# USB-8452_flash_breakout.net
KiCad netlist of a schematic drawn in EAGLE
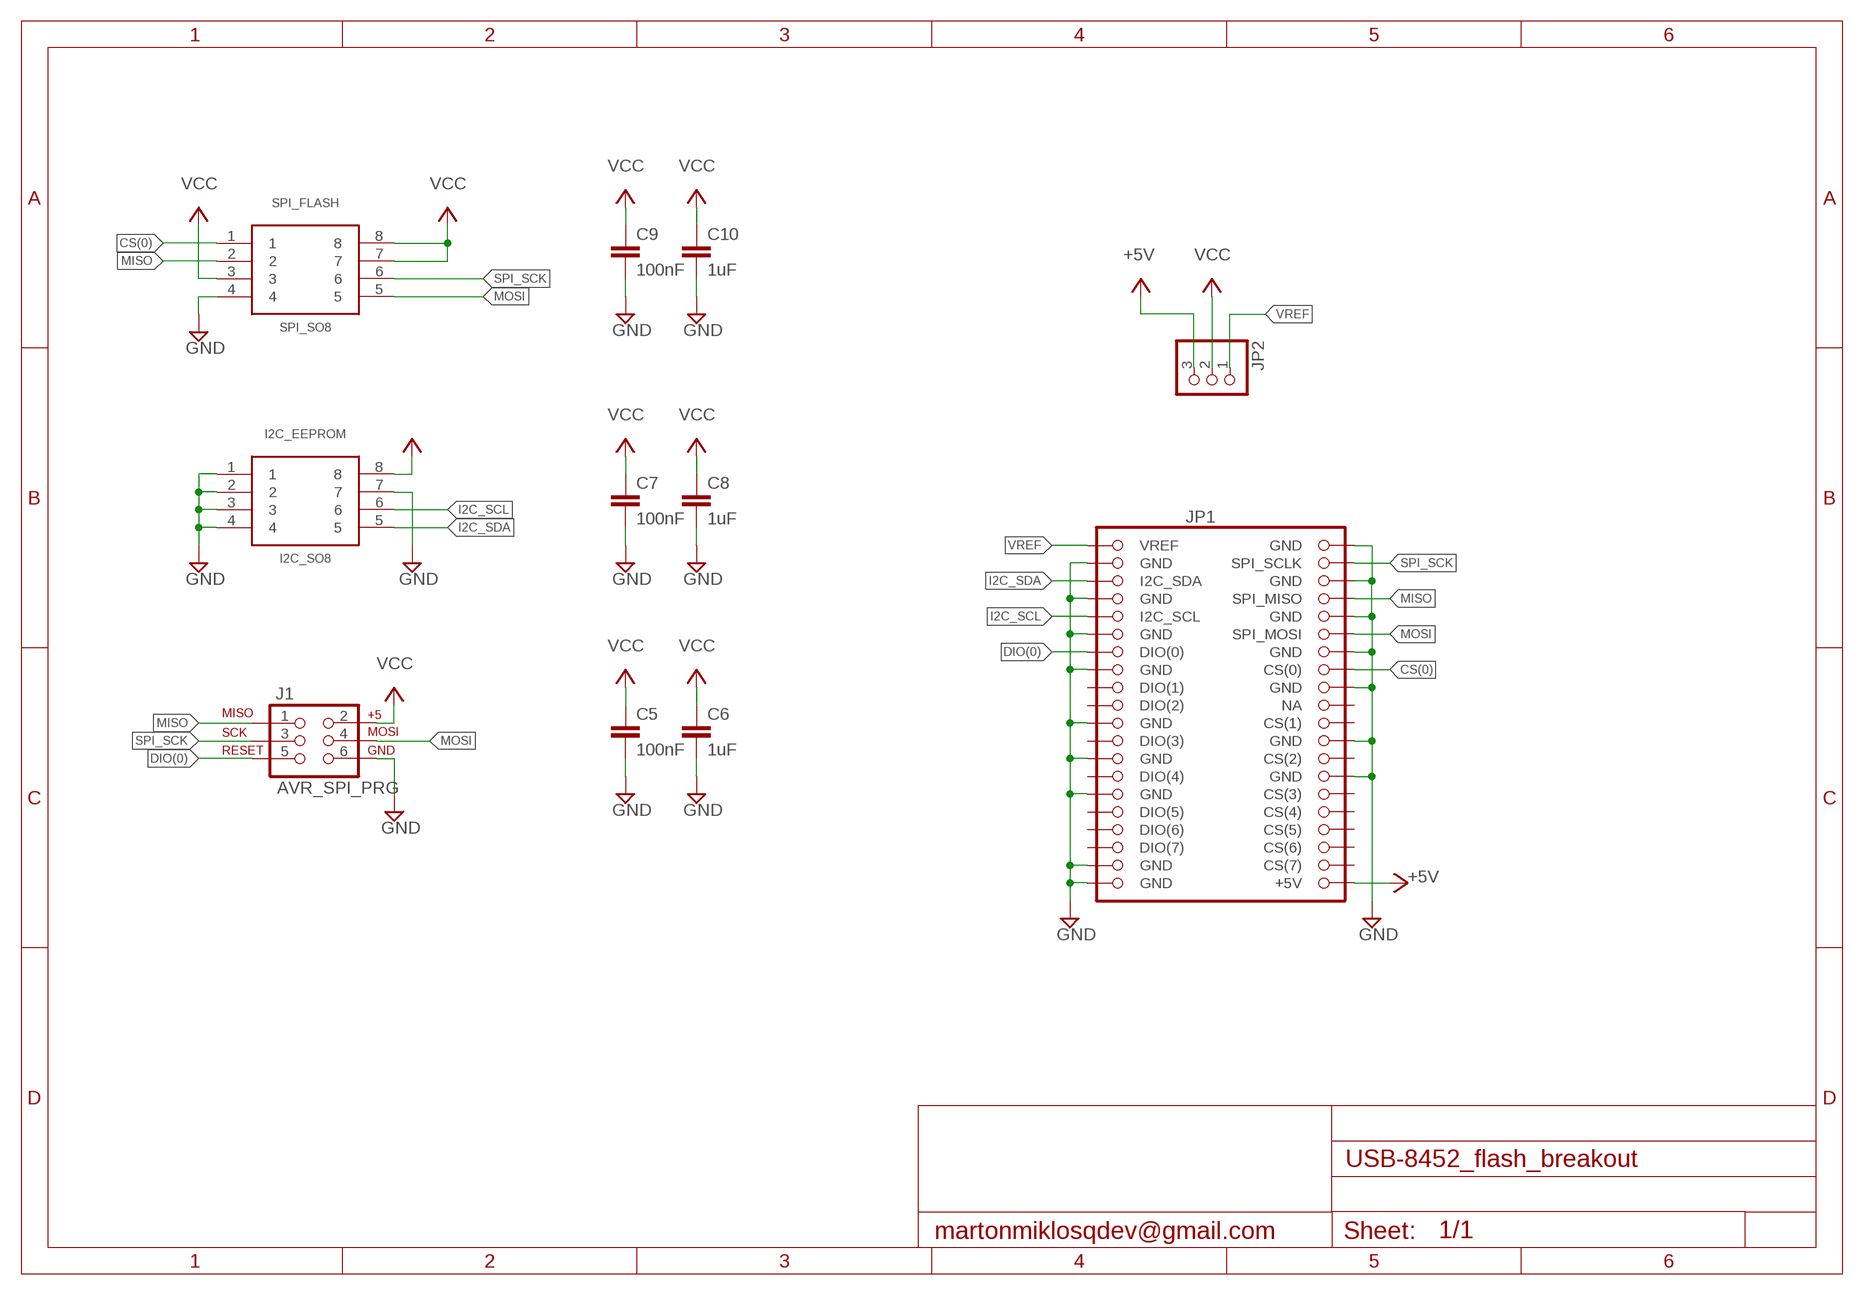
[diagram p0: schematic, sheet 1]

(export (version "E")
  (design (tool "Eeschema 10.0.6"))
  (components
    (comp (ref "C5")
      (value "100nF")
      (footprint "eagle-import:C0603")
      (libsource (lib "eagle-import") (part "C-EUC0603"))
    )
    (comp (ref "C6")
      (value "1uF")
      (footprint "eagle-import:C0603")
      (libsource (lib "eagle-import") (part "C-EUC0603"))
    )
    (comp (ref "C7")
      (value "100nF")
      (footprint "eagle-import:C0603")
      (libsource (lib "eagle-import") (part "C-EUC0603"))
    )
    (comp (ref "C8")
      (value "1uF")
      (footprint "eagle-import:C0603")
      (libsource (lib "eagle-import") (part "C-EUC0603"))
    )
    (comp (ref "C9")
      (value "100nF")
      (footprint "eagle-import:C0603")
      (libsource (lib "eagle-import") (part "C-EUC0603"))
    )
    (comp (ref "C10")
      (value "1uF")
      (footprint "eagle-import:C0603")
      (libsource (lib "eagle-import") (part "C-EUC0603"))
    )
    (comp (ref "I2C_EEPROM")
      (value "I2C_SO8")
      (footprint "eagle-import:SO8_LONG")
      (libsource (lib "eagle-import") (part "SO8_LONG"))
    )
    (comp (ref "J1")
      (value "AVR_SPI_PRG")
      (footprint "eagle-import:2X3-NS")
      (libsource (lib "eagle-import") (part "AVR_SPI_PRG_6NS"))
    )
    (comp (ref "JP1")
      (value "USB8452_HEADER")
      (footprint "eagle-import:2X20")
      (libsource (lib "eagle-import") (part "USB8452_HEADER"))
    )
    (comp (ref "JP2")
      (value "PINHD-1X3")
      (footprint "eagle-import:1X03")
      (libsource (lib "eagle-import") (part "PINHD-1X3"))
    )
    (comp (ref "SPI_FLASH")
      (value "SPI_SO8")
      (footprint "eagle-import:SO8_LONG")
      (libsource (lib "eagle-import") (part "SO8_LONG"))
    )
  )
  (nets
    (net (code "1") (name "+5V") (class "Default")
      (node (ref "JP1") (pin "40") (pinfunction "+5V_40") (pintype "passive"))
      (node (ref "JP2") (pin "3") (pinfunction "3_3") (pintype "passive"))
    )
    (net (code "2") (name "CS(0)") (class "Default")
      (node (ref "JP1") (pin "16") (pinfunction "CS(0)_16") (pintype "input"))
      (node (ref "SPI_FLASH") (pin "1") (pinfunction "1_1") (pintype "bidirectional"))
    )
    (net (code "3") (name "DIO(0)") (class "Default")
      (node (ref "J1") (pin "5") (pinfunction "5_5") (pintype "passive"))
      (node (ref "JP1") (pin "13") (pinfunction "DIO(0)_13") (pintype "bidirectional"))
    )
    (net (code "4") (name "GND") (class "Default")
      (node (ref "C10") (pin "2") (pinfunction "2_2") (pintype "passive"))
      (node (ref "C5") (pin "2") (pinfunction "2_2") (pintype "passive"))
      (node (ref "C6") (pin "2") (pinfunction "2_2") (pintype "passive"))
      (node (ref "C7") (pin "2") (pinfunction "2_2") (pintype "passive"))
      (node (ref "C8") (pin "2") (pinfunction "2_2") (pintype "passive"))
      (node (ref "C9") (pin "2") (pinfunction "2_2") (pintype "passive"))
      (node (ref "I2C_EEPROM") (pin "1") (pinfunction "1_1") (pintype "bidirectional"))
      (node (ref "I2C_EEPROM") (pin "2") (pinfunction "2_2") (pintype "bidirectional"))
      (node (ref "I2C_EEPROM") (pin "3") (pinfunction "3_3") (pintype "bidirectional"))
      (node (ref "I2C_EEPROM") (pin "4") (pinfunction "4_4") (pintype "bidirectional"))
      (node (ref "I2C_EEPROM") (pin "7") (pinfunction "7_7") (pintype "bidirectional"))
      (node (ref "J1") (pin "6") (pinfunction "6_6") (pintype "passive"))
      (node (ref "JP1") (pin "10") (pinfunction "GND_10") (pintype "passive"))
      (node (ref "JP1") (pin "11") (pinfunction "GND_11") (pintype "passive"))
      (node (ref "JP1") (pin "14") (pinfunction "GND_14") (pintype "passive"))
      (node (ref "JP1") (pin "15") (pinfunction "GND_15") (pintype "passive"))
      (node (ref "JP1") (pin "18") (pinfunction "GND_18") (pintype "passive"))
      (node (ref "JP1") (pin "2") (pinfunction "GND_2") (pintype "passive"))
      (node (ref "JP1") (pin "21") (pinfunction "GND_21") (pintype "passive"))
      (node (ref "JP1") (pin "24") (pinfunction "GND_24") (pintype "passive"))
      (node (ref "JP1") (pin "25") (pinfunction "GND_25") (pintype "passive"))
      (node (ref "JP1") (pin "28") (pinfunction "GND_28") (pintype "passive"))
      (node (ref "JP1") (pin "29") (pinfunction "GND_29") (pintype "passive"))
      (node (ref "JP1") (pin "3") (pinfunction "GND_3") (pintype "passive"))
      (node (ref "JP1") (pin "37") (pinfunction "GND_37") (pintype "passive"))
      (node (ref "JP1") (pin "39") (pinfunction "GND_39") (pintype "passive"))
      (node (ref "JP1") (pin "6") (pinfunction "GND_6") (pintype "passive"))
      (node (ref "JP1") (pin "7") (pinfunction "GND_7") (pintype "passive"))
      (node (ref "SPI_FLASH") (pin "4") (pinfunction "4_4") (pintype "bidirectional"))
    )
    (net (code "5") (name "I2C_SCL") (class "Default")
      (node (ref "I2C_EEPROM") (pin "6") (pinfunction "6_6") (pintype "bidirectional"))
      (node (ref "JP1") (pin "9") (pinfunction "I2C_SCL_9") (pintype "bidirectional"))
    )
    (net (code "6") (name "I2C_SDA") (class "Default")
      (node (ref "I2C_EEPROM") (pin "5") (pinfunction "5_5") (pintype "bidirectional"))
      (node (ref "JP1") (pin "5") (pinfunction "I2C_SDA_5") (pintype "bidirectional"))
    )
    (net (code "7") (name "MISO") (class "Default")
      (node (ref "J1") (pin "1") (pinfunction "1_1") (pintype "passive"))
      (node (ref "JP1") (pin "8") (pinfunction "SPI_MISO_8") (pintype "output"))
      (node (ref "SPI_FLASH") (pin "2") (pinfunction "2_2") (pintype "bidirectional"))
    )
    (net (code "8") (name "MOSI") (class "Default")
      (node (ref "J1") (pin "4") (pinfunction "4_4") (pintype "passive"))
      (node (ref "JP1") (pin "12") (pinfunction "SPI_MOSI_12") (pintype "input"))
      (node (ref "SPI_FLASH") (pin "5") (pinfunction "5_5") (pintype "bidirectional"))
    )
    (net (code "9") (name "SPI_SCK") (class "Default")
      (node (ref "J1") (pin "3") (pinfunction "3_3") (pintype "passive"))
      (node (ref "JP1") (pin "4") (pinfunction "SPI_SCLK_4") (pintype "input"))
      (node (ref "SPI_FLASH") (pin "6") (pinfunction "6_6") (pintype "bidirectional"))
    )
    (net (code "10") (name "VCC") (class "Default")
      (node (ref "C10") (pin "1") (pinfunction "1_1") (pintype "passive"))
      (node (ref "C5") (pin "1") (pinfunction "1_1") (pintype "passive"))
      (node (ref "C6") (pin "1") (pinfunction "1_1") (pintype "passive"))
      (node (ref "C7") (pin "1") (pinfunction "1_1") (pintype "passive"))
      (node (ref "C8") (pin "1") (pinfunction "1_1") (pintype "passive"))
      (node (ref "C9") (pin "1") (pinfunction "1_1") (pintype "passive"))
      (node (ref "I2C_EEPROM") (pin "8") (pinfunction "8_8") (pintype "bidirectional"))
      (node (ref "J1") (pin "2") (pinfunction "2_2") (pintype "passive"))
      (node (ref "JP2") (pin "2") (pinfunction "2_2") (pintype "passive"))
      (node (ref "SPI_FLASH") (pin "3") (pinfunction "3_3") (pintype "bidirectional"))
      (node (ref "SPI_FLASH") (pin "7") (pinfunction "7_7") (pintype "bidirectional"))
      (node (ref "SPI_FLASH") (pin "8") (pinfunction "8_8") (pintype "bidirectional"))
    )
    (net (code "11") (name "VREF") (class "Default")
      (node (ref "JP1") (pin "1") (pinfunction "VREF_1") (pintype "input"))
      (node (ref "JP2") (pin "1") (pinfunction "1_1") (pintype "passive"))
    )
    (net (code "12") (name "unconnected-(JP1-CS(1)-Pad22)") (class "Default")
      (node (ref "JP1") (pin "22") (pinfunction "CS(1)_22") (pintype "input"))
    )
    (net (code "13") (name "unconnected-(JP1-CS(2)-Pad26)") (class "Default")
      (node (ref "JP1") (pin "26") (pinfunction "CS(2)_26") (pintype "input"))
    )
    (net (code "14") (name "unconnected-(JP1-CS(3)-Pad30)") (class "Default")
      (node (ref "JP1") (pin "30") (pinfunction "CS(3)_30") (pintype "input"))
    )
    (net (code "15") (name "unconnected-(JP1-CS(4)-Pad32)") (class "Default")
      (node (ref "JP1") (pin "32") (pinfunction "CS(4)_32") (pintype "input"))
    )
    (net (code "16") (name "unconnected-(JP1-CS(5)-Pad34)") (class "Default")
      (node (ref "JP1") (pin "34") (pinfunction "CS(5)_34") (pintype "input"))
    )
    (net (code "17") (name "unconnected-(JP1-CS(6)-Pad36)") (class "Default")
      (node (ref "JP1") (pin "36") (pinfunction "CS(6)_36") (pintype "input"))
    )
    (net (code "18") (name "unconnected-(JP1-CS(7)-Pad38)") (class "Default")
      (node (ref "JP1") (pin "38") (pinfunction "CS(7)_38") (pintype "input"))
    )
    (net (code "19") (name "unconnected-(JP1-DIO(1)-Pad17)") (class "Default")
      (node (ref "JP1") (pin "17") (pinfunction "DIO(1)_17") (pintype "bidirectional"))
    )
    (net (code "20") (name "unconnected-(JP1-DIO(2)-Pad19)") (class "Default")
      (node (ref "JP1") (pin "19") (pinfunction "DIO(2)_19") (pintype "bidirectional"))
    )
    (net (code "21") (name "unconnected-(JP1-DIO(3)-Pad23)") (class "Default")
      (node (ref "JP1") (pin "23") (pinfunction "DIO(3)_23") (pintype "bidirectional"))
    )
    (net (code "22") (name "unconnected-(JP1-DIO(4)-Pad27)") (class "Default")
      (node (ref "JP1") (pin "27") (pinfunction "DIO(4)_27") (pintype "passive"))
    )
    (net (code "23") (name "unconnected-(JP1-DIO(5)-Pad31)") (class "Default")
      (node (ref "JP1") (pin "31") (pinfunction "DIO(5)_31") (pintype "bidirectional"))
    )
    (net (code "24") (name "unconnected-(JP1-DIO(6)-Pad33)") (class "Default")
      (node (ref "JP1") (pin "33") (pinfunction "DIO(6)_33") (pintype "bidirectional"))
    )
    (net (code "25") (name "unconnected-(JP1-DIO(7)-Pad35)") (class "Default")
      (node (ref "JP1") (pin "35") (pinfunction "DIO(7)_35") (pintype "bidirectional"))
    )
    (net (code "26") (name "unconnected-(JP1-NA-Pad20)") (class "Default")
      (node (ref "JP1") (pin "20") (pinfunction "NA_20") (pintype "no_connect"))
    )
  )
)
